# RPI-CM4-Breakout.net
KiCad netlist of a schematic drawn in EAGLE
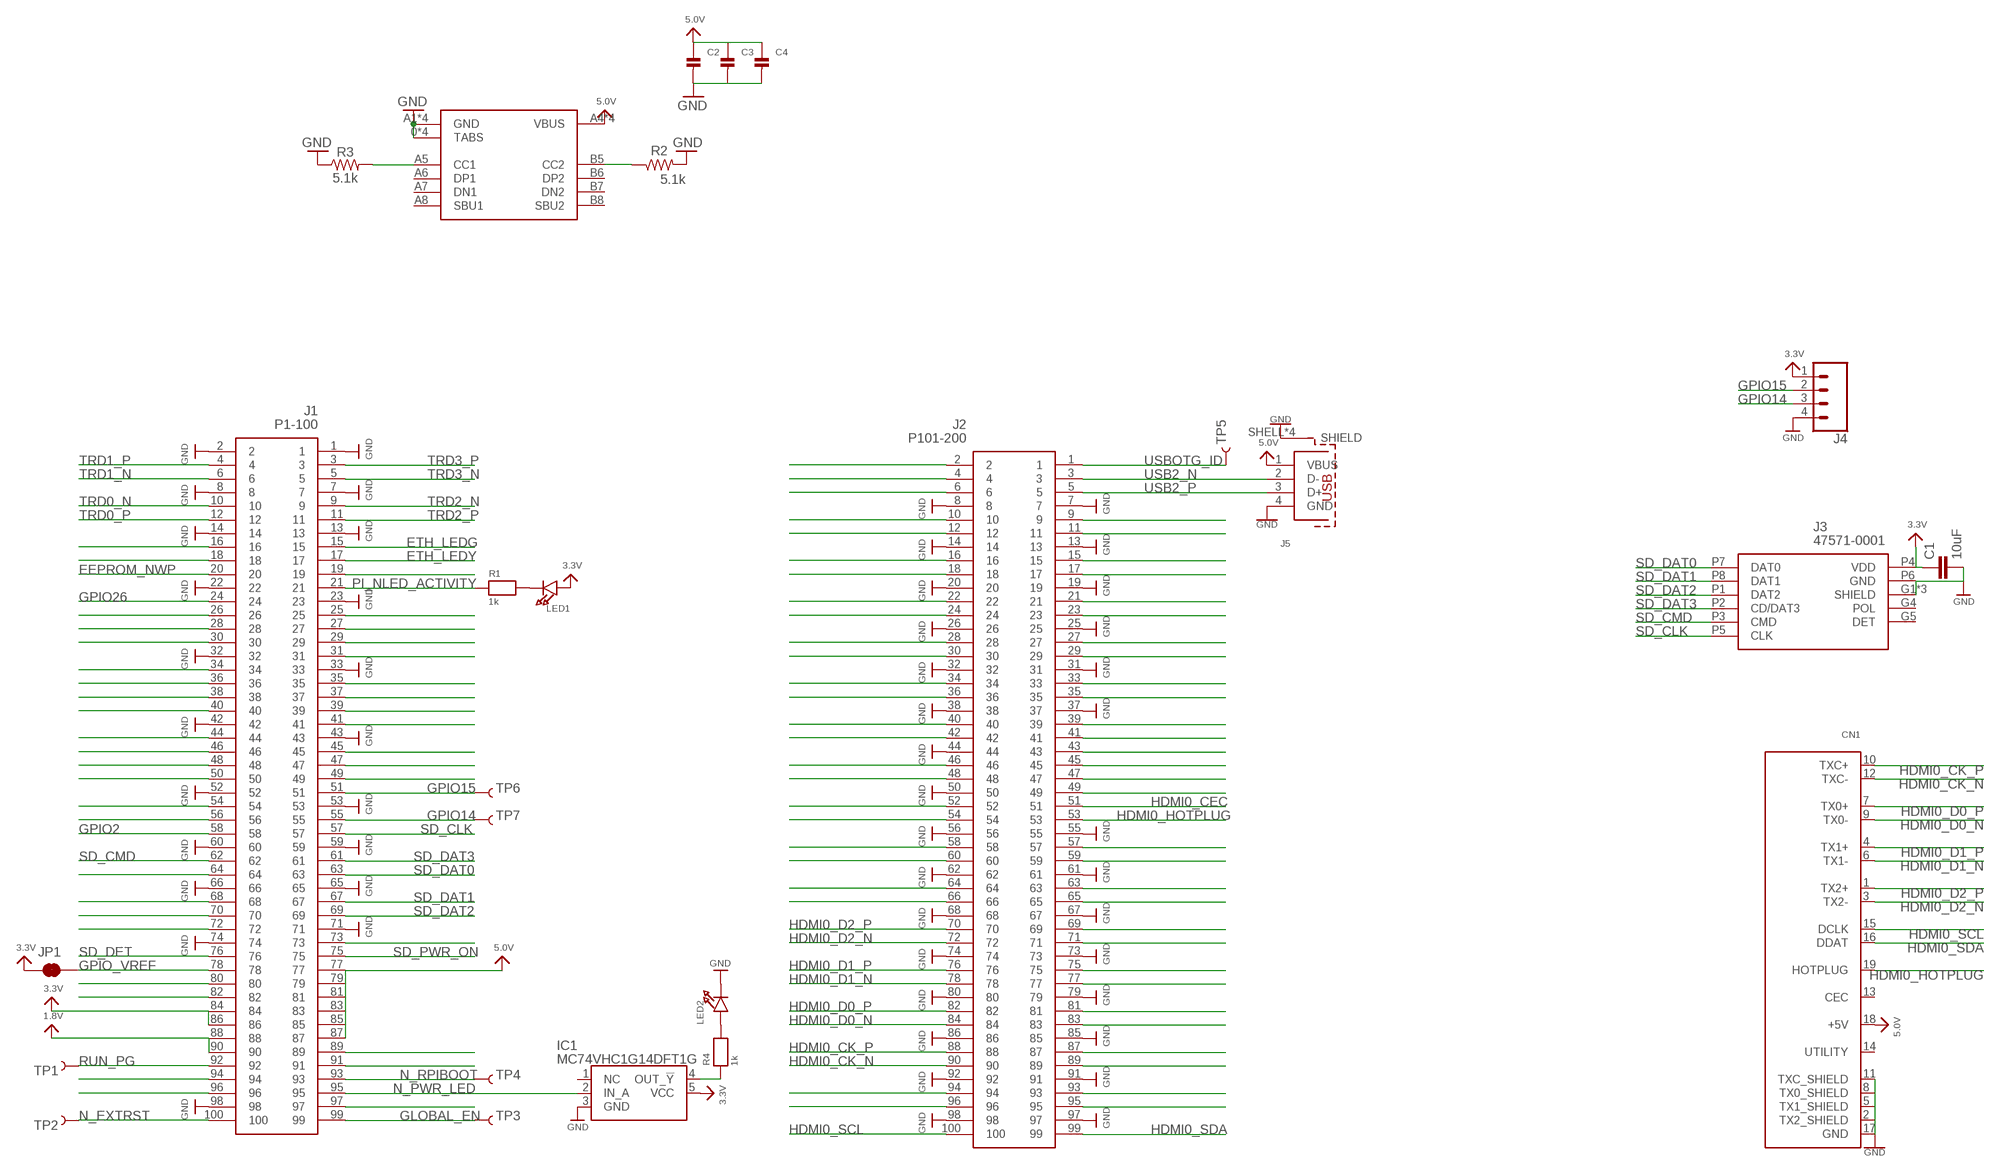
[diagram p0: schematic, sheet 1]

(export (version "E")
  (design (tool "Eeschema 10.0.6"))
  (components
    (comp (ref "C1")
      (value "10uF")
      (footprint "eagle-import:0603")
      (libsource (lib "eagle-import") (part "10UF-0603-6.3V-20%"))
    )
    (comp (ref "C2")
      (value "CAP_CERAMIC0402")
      (footprint "eagle-import:0402")
      (libsource (lib "eagle-import") (part "CAP_CERAMIC0402"))
    )
    (comp (ref "C3")
      (value "CAP_CERAMIC0402")
      (footprint "eagle-import:0402")
      (libsource (lib "eagle-import") (part "CAP_CERAMIC0402"))
    )
    (comp (ref "C4")
      (value "CAP_CERAMIC0402")
      (footprint "eagle-import:0402")
      (libsource (lib "eagle-import") (part "CAP_CERAMIC0402"))
    )
    (comp (ref "CN1")
      (value "HDMI_MOLEX_47151-0001")
      (footprint "eagle-import:HDMI_MOLEX_47151-0001")
      (libsource (lib "eagle-import") (part "HDMI_MOLEX_47151-0001"))
    )
    (comp (ref "IC1")
      (value "MC74VHC1G14DFT1G")
      (footprint "eagle-import:SOT65P210X110-5N")
      (fields (field (name "MOUSER_PART_NUMBER") "863-MC74VHC1G14DFT1G"))
      (libsource (lib "eagle-import") (part "MC74VHC1G14DFT1G"))
    )
    (comp (ref "J1")
      (value "P1-100")
      (footprint "eagle-import:DF40C100DS04V51")
      (fields
        (field (name "MANUFACTURER_PART_NUMBER") "DF40C-100DS-0.4V(51)")
        (field (name "MOUSER_PART_NUMBER") "798-DF40C100DS0.4V51")
      )
      (libsource (lib "eagle-import") (part "DF40C-100DS-0.4V_51_"))
    )
    (comp (ref "J2")
      (value "P101-200")
      (footprint "eagle-import:DF40C100DS04V51")
      (fields
        (field (name "MANUFACTURER_PART_NUMBER") "DF40C-100DS-0.4V(51)")
        (field (name "MOUSER_PART_NUMBER") "798-DF40C100DS0.4V51")
      )
      (libsource (lib "eagle-import") (part "DF40C-100DS-0.4V_51_"))
    )
    (comp (ref "J3")
      (value "47571-0001")
      (footprint "eagle-import:47571-0001")
      (fields (field (name "MOUSER_PART_NUMBER") "538-47571-0001"))
      (libsource (lib "eagle-import") (part "47571-0001"))
    )
    (comp (ref "J4")
      (value "CONN_04SMD_RA_FEMALE")
      (footprint "eagle-import:1X04_SMD_RA_FEMALE")
      (libsource (lib "eagle-import") (part "CONN_04SMD_RA_FEMALE"))
    )
    (comp (ref "J5")
      (value "629104190121")
      (footprint "eagle-import:629104190121")
      (libsource (lib "eagle-import") (part "629104190121"))
    )
    (comp (ref "JP1")
      (value "JUMPER-SMT_2_NC_TRACE_NO-SILK")
      (footprint "eagle-import:SMT-JUMPER_2_NC_TRACE_NO-SILK")
      (libsource (lib "eagle-import") (part "JUMPER-SMT_2_NC_TRACE_NO-SILK"))
    )
    (comp (ref "LED1")
      (value "LED0603")
      (footprint "eagle-import:CHIPLED_0603")
      (libsource (lib "eagle-import") (part "LED0603"))
    )
    (comp (ref "LED2")
      (value "LED0603")
      (footprint "eagle-import:CHIPLED_0603")
      (libsource (lib "eagle-import") (part "LED0603"))
    )
    (comp (ref "R1")
      (value "1k")
      (footprint "eagle-import:_0402MP")
      (libsource (lib "eagle-import") (part "RESISTOR_0402MP"))
    )
    (comp (ref "R2")
      (value "5.1k")
      (footprint "eagle-import:0603")
      (libsource (lib "eagle-import") (part "RESISTOR0603"))
    )
    (comp (ref "R3")
      (value "5.1k")
      (footprint "eagle-import:0603")
      (libsource (lib "eagle-import") (part "RESISTOR0603"))
    )
    (comp (ref "R4")
      (value "1k")
      (footprint "eagle-import:_0402MP")
      (libsource (lib "eagle-import") (part "RESISTOR_0402MP"))
    )
    (comp (ref "TP1")
      (value "TEST-POINT3X5")
      (footprint "eagle-import:PAD.03X.05")
      (libsource (lib "eagle-import") (part "TEST-POINT3X5"))
    )
    (comp (ref "TP2")
      (value "TEST-POINT3X5")
      (footprint "eagle-import:PAD.03X.05")
      (libsource (lib "eagle-import") (part "TEST-POINT3X5"))
    )
    (comp (ref "TP3")
      (value "TEST-POINT3X5")
      (footprint "eagle-import:PAD.03X.05")
      (libsource (lib "eagle-import") (part "TEST-POINT3X5"))
    )
    (comp (ref "TP4")
      (value "TEST-POINT3X5")
      (footprint "eagle-import:PAD.03X.05")
      (libsource (lib "eagle-import") (part "TEST-POINT3X5"))
    )
    (comp (ref "TP5")
      (value "TEST-POINT3X5")
      (footprint "eagle-import:PAD.03X.05")
      (libsource (lib "eagle-import") (part "TEST-POINT3X5"))
    )
    (comp (ref "TP6")
      (value "TEST-POINT3X5")
      (footprint "eagle-import:PAD.03X.05")
      (libsource (lib "eagle-import") (part "TEST-POINT3X5"))
    )
    (comp (ref "TP7")
      (value "TEST-POINT3X5")
      (footprint "eagle-import:PAD.03X.05")
      (libsource (lib "eagle-import") (part "TEST-POINT3X5"))
    )
    (comp (ref "U$59")
      (value "TYPE-C-31-M-12")
      (footprint "eagle-import:USB-TYPE-C_16PIN-MALE-TYPE-C-31-M-12")
      (libsource (lib "eagle-import") (part "TYPE-C-31-M-12"))
    )
  )
  (nets
    (net (code "1") (name "/EEPROM_NWP") (class "Default")
      (node (ref "J1") (pin "20") (pinfunction "20_20") (pintype "bidirectional"))
    )
    (net (code "2") (name "/ETH_LEDG") (class "Default")
      (node (ref "J1") (pin "15") (pinfunction "15_15") (pintype "bidirectional"))
    )
    (net (code "3") (name "/ETH_LEDY") (class "Default")
      (node (ref "J1") (pin "17") (pinfunction "17_17") (pintype "bidirectional"))
    )
    (net (code "4") (name "/GLOBAL_EN") (class "Default")
      (node (ref "J1") (pin "99") (pinfunction "99_99") (pintype "bidirectional"))
      (node (ref "TP3") (pin "P$1") (pinfunction "1_P$1") (pintype "bidirectional"))
    )
    (net (code "5") (name "/GPIO2") (class "Default")
      (node (ref "J1") (pin "58") (pinfunction "58_58") (pintype "bidirectional"))
    )
    (net (code "6") (name "/GPIO14") (class "Default")
      (node (ref "J1") (pin "55") (pinfunction "55_55") (pintype "bidirectional"))
      (node (ref "J4") (pin "3") (pinfunction "3_3") (pintype "passive"))
      (node (ref "TP7") (pin "P$1") (pinfunction "1_P$1") (pintype "bidirectional"))
    )
    (net (code "7") (name "/GPIO15") (class "Default")
      (node (ref "J1") (pin "51") (pinfunction "51_51") (pintype "bidirectional"))
      (node (ref "J4") (pin "2") (pinfunction "2_2") (pintype "passive"))
      (node (ref "TP6") (pin "P$1") (pinfunction "1_P$1") (pintype "bidirectional"))
    )
    (net (code "8") (name "/GPIO26") (class "Default")
      (node (ref "J1") (pin "24") (pinfunction "24_24") (pintype "bidirectional"))
    )
    (net (code "9") (name "/GPIO_VREF") (class "Default")
      (node (ref "J1") (pin "78") (pinfunction "78_78") (pintype "bidirectional"))
      (node (ref "JP1") (pin "2") (pinfunction "2_2") (pintype "passive"))
    )
    (net (code "10") (name "/HDMI0_CEC") (class "Default")
      (node (ref "J2") (pin "51") (pinfunction "51_51") (pintype "bidirectional"))
    )
    (net (code "11") (name "/HDMI0_CK_N") (class "Default")
      (node (ref "CN1") (pin "12") (pinfunction "TXC-_12") (pintype "bidirectional"))
      (node (ref "J2") (pin "90") (pinfunction "90_90") (pintype "bidirectional"))
    )
    (net (code "12") (name "/HDMI0_CK_P") (class "Default")
      (node (ref "CN1") (pin "10") (pinfunction "TXC+_10") (pintype "bidirectional"))
      (node (ref "J2") (pin "88") (pinfunction "88_88") (pintype "bidirectional"))
    )
    (net (code "13") (name "/HDMI0_D0_N") (class "Default")
      (node (ref "CN1") (pin "9") (pinfunction "TX0-_9") (pintype "bidirectional"))
      (node (ref "J2") (pin "84") (pinfunction "84_84") (pintype "bidirectional"))
    )
    (net (code "14") (name "/HDMI0_D0_P") (class "Default")
      (node (ref "CN1") (pin "7") (pinfunction "TX0+_7") (pintype "bidirectional"))
      (node (ref "J2") (pin "82") (pinfunction "82_82") (pintype "bidirectional"))
    )
    (net (code "15") (name "/HDMI0_D1_N") (class "Default")
      (node (ref "CN1") (pin "6") (pinfunction "TX1-_6") (pintype "bidirectional"))
      (node (ref "J2") (pin "78") (pinfunction "78_78") (pintype "bidirectional"))
    )
    (net (code "16") (name "/HDMI0_D1_P") (class "Default")
      (node (ref "CN1") (pin "4") (pinfunction "TX1+_4") (pintype "bidirectional"))
      (node (ref "J2") (pin "76") (pinfunction "76_76") (pintype "bidirectional"))
    )
    (net (code "17") (name "/HDMI0_D2_N") (class "Default")
      (node (ref "CN1") (pin "3") (pinfunction "TX2-_3") (pintype "bidirectional"))
      (node (ref "J2") (pin "72") (pinfunction "72_72") (pintype "bidirectional"))
    )
    (net (code "18") (name "/HDMI0_D2_P") (class "Default")
      (node (ref "CN1") (pin "1") (pinfunction "TX2+_1") (pintype "bidirectional"))
      (node (ref "J2") (pin "70") (pinfunction "70_70") (pintype "bidirectional"))
    )
    (net (code "19") (name "/HDMI0_HOTPLUG") (class "Default")
      (node (ref "CN1") (pin "19") (pinfunction "HOTPLUG_19") (pintype "bidirectional"))
      (node (ref "J2") (pin "53") (pinfunction "53_53") (pintype "bidirectional"))
    )
    (net (code "20") (name "/HDMI0_SCL") (class "Default")
      (node (ref "CN1") (pin "15") (pinfunction "DCLK_15") (pintype "bidirectional"))
      (node (ref "J2") (pin "100") (pinfunction "100_100") (pintype "bidirectional"))
    )
    (net (code "21") (name "/HDMI0_SDA") (class "Default")
      (node (ref "CN1") (pin "16") (pinfunction "DDAT_16") (pintype "bidirectional"))
      (node (ref "J2") (pin "99") (pinfunction "99_99") (pintype "bidirectional"))
    )
    (net (code "22") (name "/N_EXTRST") (class "Default")
      (node (ref "J1") (pin "100") (pinfunction "100_100") (pintype "bidirectional"))
      (node (ref "TP2") (pin "P$1") (pinfunction "1_P$1") (pintype "bidirectional"))
    )
    (net (code "23") (name "/N_PWR_LED") (class "Default")
      (node (ref "IC1") (pin "2") (pinfunction "IN_A_2") (pintype "input"))
      (node (ref "J1") (pin "95") (pinfunction "95_95") (pintype "bidirectional"))
    )
    (net (code "24") (name "/N_RPIBOOT") (class "Default")
      (node (ref "J1") (pin "93") (pinfunction "93_93") (pintype "bidirectional"))
      (node (ref "TP4") (pin "P$1") (pinfunction "1_P$1") (pintype "bidirectional"))
    )
    (net (code "25") (name "/PI_NLED_ACTIVITY") (class "Default")
      (node (ref "J1") (pin "21") (pinfunction "21_21") (pintype "bidirectional"))
      (node (ref "R1") (pin "1") (pinfunction "1_1") (pintype "passive"))
    )
    (net (code "26") (name "/RUN_PG") (class "Default")
      (node (ref "J1") (pin "92") (pinfunction "92_92") (pintype "bidirectional"))
      (node (ref "TP1") (pin "P$1") (pinfunction "1_P$1") (pintype "bidirectional"))
    )
    (net (code "27") (name "/SD_CLK") (class "Default")
      (node (ref "J1") (pin "57") (pinfunction "57_57") (pintype "bidirectional"))
      (node (ref "J3") (pin "P5") (pinfunction "CLK_P5") (pintype "bidirectional"))
    )
    (net (code "28") (name "/SD_CMD") (class "Default")
      (node (ref "J1") (pin "62") (pinfunction "62_62") (pintype "bidirectional"))
      (node (ref "J3") (pin "P3") (pinfunction "CMD_P3") (pintype "bidirectional"))
    )
    (net (code "29") (name "/SD_DAT0") (class "Default")
      (node (ref "J1") (pin "63") (pinfunction "63_63") (pintype "bidirectional"))
      (node (ref "J3") (pin "P7") (pinfunction "DAT0_P7") (pintype "bidirectional"))
    )
    (net (code "30") (name "/SD_DAT1") (class "Default")
      (node (ref "J1") (pin "67") (pinfunction "67_67") (pintype "bidirectional"))
      (node (ref "J3") (pin "P8") (pinfunction "DAT1_P8") (pintype "bidirectional"))
    )
    (net (code "31") (name "/SD_DAT2") (class "Default")
      (node (ref "J1") (pin "69") (pinfunction "69_69") (pintype "bidirectional"))
      (node (ref "J3") (pin "P1") (pinfunction "DAT2_P1") (pintype "bidirectional"))
    )
    (net (code "32") (name "/SD_DAT3") (class "Default")
      (node (ref "J1") (pin "61") (pinfunction "61_61") (pintype "bidirectional"))
      (node (ref "J3") (pin "P2") (pinfunction "CD/DAT3_P2") (pintype "bidirectional"))
    )
    (net (code "33") (name "/SD_DET") (class "Default")
      (node (ref "J1") (pin "76") (pinfunction "76_76") (pintype "bidirectional"))
    )
    (net (code "34") (name "/SD_PWR_ON") (class "Default")
      (node (ref "J1") (pin "75") (pinfunction "75_75") (pintype "bidirectional"))
    )
    (net (code "35") (name "/TRD0_N") (class "Default")
      (node (ref "J1") (pin "10") (pinfunction "10_10") (pintype "bidirectional"))
    )
    (net (code "36") (name "/TRD0_P") (class "Default")
      (node (ref "J1") (pin "12") (pinfunction "12_12") (pintype "bidirectional"))
    )
    (net (code "37") (name "/TRD1_N") (class "Default")
      (node (ref "J1") (pin "6") (pinfunction "6_6") (pintype "bidirectional"))
    )
    (net (code "38") (name "/TRD1_P") (class "Default")
      (node (ref "J1") (pin "4") (pinfunction "4_4") (pintype "bidirectional"))
    )
    (net (code "39") (name "/TRD2_N") (class "Default")
      (node (ref "J1") (pin "9") (pinfunction "9_9") (pintype "bidirectional"))
    )
    (net (code "40") (name "/TRD2_P") (class "Default")
      (node (ref "J1") (pin "11") (pinfunction "11_11") (pintype "bidirectional"))
    )
    (net (code "41") (name "/TRD3_N") (class "Default")
      (node (ref "J1") (pin "5") (pinfunction "5_5") (pintype "bidirectional"))
    )
    (net (code "42") (name "/TRD3_P") (class "Default")
      (node (ref "J1") (pin "3") (pinfunction "3_3") (pintype "bidirectional"))
    )
    (net (code "43") (name "/USB2_N") (class "Default")
      (node (ref "J2") (pin "3") (pinfunction "3_3") (pintype "bidirectional"))
      (node (ref "J5") (pin "2") (pinfunction "D-_2") (pintype "bidirectional"))
    )
    (net (code "44") (name "/USB2_P") (class "Default")
      (node (ref "J2") (pin "5") (pinfunction "5_5") (pintype "bidirectional"))
      (node (ref "J5") (pin "3") (pinfunction "D+_3") (pintype "bidirectional"))
    )
    (net (code "45") (name "/USBOTG_ID") (class "Default")
      (node (ref "J2") (pin "1") (pinfunction "1_1") (pintype "bidirectional"))
      (node (ref "TP5") (pin "P$1") (pinfunction "1_P$1") (pintype "bidirectional"))
    )
    (net (code "46") (name "1.8V") (class "Default")
      (node (ref "J1") (pin "88") (pinfunction "88_88") (pintype "bidirectional"))
      (node (ref "J1") (pin "90") (pinfunction "90_90") (pintype "bidirectional"))
    )
    (net (code "47") (name "3.3V") (class "Default")
      (node (ref "C1") (pin "1") (pinfunction "1_1") (pintype "passive"))
      (node (ref "IC1") (pin "5") (pinfunction "VCC_5") (pintype "power_in"))
      (node (ref "J1") (pin "84") (pinfunction "84_84") (pintype "bidirectional"))
      (node (ref "J1") (pin "86") (pinfunction "86_86") (pintype "bidirectional"))
      (node (ref "J3") (pin "P4") (pinfunction "VDD_P4") (pintype "bidirectional"))
      (node (ref "J4") (pin "1") (pinfunction "1_1") (pintype "passive"))
      (node (ref "JP1") (pin "1") (pinfunction "1_1") (pintype "passive"))
      (node (ref "LED1") (pin "A") (pinfunction "A_A") (pintype "passive"))
    )
    (net (code "48") (name "5.0V") (class "Default")
      (node (ref "C2") (pin "1") (pinfunction "P$1_1") (pintype "passive"))
      (node (ref "C3") (pin "1") (pinfunction "P$1_1") (pintype "passive"))
      (node (ref "C4") (pin "1") (pinfunction "P$1_1") (pintype "passive"))
      (node (ref "CN1") (pin "18") (pinfunction "+5V_18") (pintype "power_in"))
      (node (ref "J1") (pin "77") (pinfunction "77_77") (pintype "bidirectional"))
      (node (ref "J1") (pin "79") (pinfunction "79_79") (pintype "bidirectional"))
      (node (ref "J1") (pin "81") (pinfunction "81_81") (pintype "bidirectional"))
      (node (ref "J1") (pin "83") (pinfunction "83_83") (pintype "bidirectional"))
      (node (ref "J1") (pin "85") (pinfunction "85_85") (pintype "bidirectional"))
      (node (ref "J1") (pin "87") (pinfunction "87_87") (pintype "bidirectional"))
      (node (ref "J5") (pin "1") (pinfunction "VBUS_1") (pintype "bidirectional"))
      (node (ref "U$59") (pin "A4") (pinfunction "VBUS_A4") (pintype "bidirectional"))
      (node (ref "U$59") (pin "A9") (pinfunction "VBUS_A9") (pintype "bidirectional"))
      (node (ref "U$59") (pin "B4") (pinfunction "VBUS_B4") (pintype "bidirectional"))
      (node (ref "U$59") (pin "B9") (pinfunction "VBUS_B9") (pintype "bidirectional"))
    )
    (net (code "49") (name "GND") (class "Default")
      (node (ref "C1") (pin "2") (pinfunction "2_2") (pintype "passive"))
      (node (ref "C2") (pin "2") (pinfunction "P$2_2") (pintype "passive"))
      (node (ref "C3") (pin "2") (pinfunction "P$2_2") (pintype "passive"))
      (node (ref "C4") (pin "2") (pinfunction "P$2_2") (pintype "passive"))
      (node (ref "CN1") (pin "11") (pinfunction "TXC_SHIELD_11") (pintype "power_in"))
      (node (ref "CN1") (pin "17") (pinfunction "GND_17") (pintype "power_in"))
      (node (ref "CN1") (pin "2") (pinfunction "TX2_SHIELD_2") (pintype "power_in"))
      (node (ref "CN1") (pin "5") (pinfunction "TX1_SHIELD_5") (pintype "power_in"))
      (node (ref "CN1") (pin "8") (pinfunction "TX0_SHIELD_8") (pintype "power_in"))
      (node (ref "IC1") (pin "3") (pinfunction "GND_3") (pintype "power_in"))
      (node (ref "J1") (pin "1") (pinfunction "1_1") (pintype "bidirectional"))
      (node (ref "J1") (pin "13") (pinfunction "13_13") (pintype "bidirectional"))
      (node (ref "J1") (pin "14") (pinfunction "14_14") (pintype "bidirectional"))
      (node (ref "J1") (pin "2") (pinfunction "2_2") (pintype "bidirectional"))
      (node (ref "J1") (pin "22") (pinfunction "22_22") (pintype "bidirectional"))
      (node (ref "J1") (pin "23") (pinfunction "23_23") (pintype "bidirectional"))
      (node (ref "J1") (pin "32") (pinfunction "32_32") (pintype "bidirectional"))
      (node (ref "J1") (pin "33") (pinfunction "33_33") (pintype "bidirectional"))
      (node (ref "J1") (pin "42") (pinfunction "42_42") (pintype "bidirectional"))
      (node (ref "J1") (pin "43") (pinfunction "43_43") (pintype "bidirectional"))
      (node (ref "J1") (pin "52") (pinfunction "52_52") (pintype "bidirectional"))
      (node (ref "J1") (pin "53") (pinfunction "53_53") (pintype "bidirectional"))
      (node (ref "J1") (pin "59") (pinfunction "59_59") (pintype "bidirectional"))
      (node (ref "J1") (pin "60") (pinfunction "60_60") (pintype "bidirectional"))
      (node (ref "J1") (pin "65") (pinfunction "65_65") (pintype "bidirectional"))
      (node (ref "J1") (pin "66") (pinfunction "66_66") (pintype "bidirectional"))
      (node (ref "J1") (pin "7") (pinfunction "7_7") (pintype "bidirectional"))
      (node (ref "J1") (pin "71") (pinfunction "71_71") (pintype "bidirectional"))
      (node (ref "J1") (pin "74") (pinfunction "74_74") (pintype "bidirectional"))
      (node (ref "J1") (pin "8") (pinfunction "8_8") (pintype "bidirectional"))
      (node (ref "J1") (pin "98") (pinfunction "98_98") (pintype "bidirectional"))
      (node (ref "J2") (pin "13") (pinfunction "13_13") (pintype "bidirectional"))
      (node (ref "J2") (pin "14") (pinfunction "14_14") (pintype "bidirectional"))
      (node (ref "J2") (pin "19") (pinfunction "19_19") (pintype "bidirectional"))
      (node (ref "J2") (pin "20") (pinfunction "20_20") (pintype "bidirectional"))
      (node (ref "J2") (pin "25") (pinfunction "25_25") (pintype "bidirectional"))
      (node (ref "J2") (pin "26") (pinfunction "26_26") (pintype "bidirectional"))
      (node (ref "J2") (pin "31") (pinfunction "31_31") (pintype "bidirectional"))
      (node (ref "J2") (pin "32") (pinfunction "32_32") (pintype "bidirectional"))
      (node (ref "J2") (pin "37") (pinfunction "37_37") (pintype "bidirectional"))
      (node (ref "J2") (pin "38") (pinfunction "38_38") (pintype "bidirectional"))
      (node (ref "J2") (pin "44") (pinfunction "44_44") (pintype "bidirectional"))
      (node (ref "J2") (pin "50") (pinfunction "50_50") (pintype "bidirectional"))
      (node (ref "J2") (pin "55") (pinfunction "55_55") (pintype "bidirectional"))
      (node (ref "J2") (pin "56") (pinfunction "56_56") (pintype "bidirectional"))
      (node (ref "J2") (pin "61") (pinfunction "61_61") (pintype "bidirectional"))
      (node (ref "J2") (pin "62") (pinfunction "62_62") (pintype "bidirectional"))
      (node (ref "J2") (pin "67") (pinfunction "67_67") (pintype "bidirectional"))
      (node (ref "J2") (pin "68") (pinfunction "68_68") (pintype "bidirectional"))
      (node (ref "J2") (pin "7") (pinfunction "7_7") (pintype "bidirectional"))
      (node (ref "J2") (pin "73") (pinfunction "73_73") (pintype "bidirectional"))
      (node (ref "J2") (pin "74") (pinfunction "74_74") (pintype "bidirectional"))
      (node (ref "J2") (pin "79") (pinfunction "79_79") (pintype "bidirectional"))
      (node (ref "J2") (pin "8") (pinfunction "8_8") (pintype "bidirectional"))
      (node (ref "J2") (pin "80") (pinfunction "80_80") (pintype "bidirectional"))
      (node (ref "J2") (pin "85") (pinfunction "85_85") (pintype "bidirectional"))
      (node (ref "J2") (pin "86") (pinfunction "86_86") (pintype "bidirectional"))
      (node (ref "J2") (pin "91") (pinfunction "91_91") (pintype "bidirectional"))
      (node (ref "J2") (pin "92") (pinfunction "92_92") (pintype "bidirectional"))
      (node (ref "J2") (pin "97") (pinfunction "97_97") (pintype "bidirectional"))
      (node (ref "J2") (pin "98") (pinfunction "98_98") (pintype "bidirectional"))
      (node (ref "J3") (pin "G1") (pinfunction "SHIELD_G1") (pintype "bidirectional"))
      (node (ref "J3") (pin "G2") (pinfunction "SHIELD_G2") (pintype "bidirectional"))
      (node (ref "J3") (pin "G3") (pinfunction "SHIELD_G3") (pintype "bidirectional"))
      (node (ref "J3") (pin "P6") (pinfunction "GND_P6") (pintype "bidirectional"))
      (node (ref "J4") (pin "4") (pinfunction "4_4") (pintype "passive"))
      (node (ref "J5") (pin "4") (pinfunction "GND_4") (pintype "bidirectional"))
      (node (ref "J5") (pin "SHELL") (pinfunction "SHIELD_SHELL") (pintype "bidirectional"))
      (node (ref "J5") (pin "SHELL1") (pinfunction "SHIELD_SHELL1") (pintype "bidirectional"))
      (node (ref "J5") (pin "SHELL2") (pinfunction "SHIELD_SHELL2") (pintype "bidirectional"))
      (node (ref "J5") (pin "SHELL3") (pinfunction "SHIELD_SHELL3") (pintype "bidirectional"))
      (node (ref "LED2") (pin "C") (pinfunction "C_C") (pintype "passive"))
      (node (ref "R2") (pin "2") (pinfunction "2_2") (pintype "passive"))
      (node (ref "R3") (pin "1") (pinfunction "1_1") (pintype "passive"))
      (node (ref "U$59") (pin "0") (pinfunction "TABS_0") (pintype "bidirectional"))
      (node (ref "U$59") (pin "0-1") (pinfunction "TABS_0-1") (pintype "bidirectional"))
      (node (ref "U$59") (pin "0-2") (pinfunction "TABS_0-2") (pintype "bidirectional"))
      (node (ref "U$59") (pin "0-3") (pinfunction "TABS_0-3") (pintype "bidirectional"))
      (node (ref "U$59") (pin "A1") (pinfunction "GND_A1") (pintype "bidirectional"))
      (node (ref "U$59") (pin "A12") (pinfunction "GND_A12") (pintype "bidirectional"))
      (node (ref "U$59") (pin "B1") (pinfunction "GND_B1") (pintype "bidirectional"))
      (node (ref "U$59") (pin "B12") (pinfunction "GND_B12") (pintype "bidirectional"))
    )
    (net (code "50") (name "Net-(IC1-OUT_~{Y})") (class "Default")
      (node (ref "IC1") (pin "4") (pinfunction "OUT_~{Y}_4") (pintype "output"))
      (node (ref "R4") (pin "1") (pinfunction "1_1") (pintype "passive"))
    )
    (net (code "51") (name "Net-(LED1-PadC)") (class "Default")
      (node (ref "LED1") (pin "C") (pinfunction "C_C") (pintype "passive"))
      (node (ref "R1") (pin "2") (pinfunction "2_2") (pintype "passive"))
    )
    (net (code "52") (name "Net-(LED2-PadA)") (class "Default")
      (node (ref "LED2") (pin "A") (pinfunction "A_A") (pintype "passive"))
      (node (ref "R4") (pin "2") (pinfunction "2_2") (pintype "passive"))
    )
    (net (code "53") (name "Net-(U$59-CC1)") (class "Default")
      (node (ref "R3") (pin "2") (pinfunction "2_2") (pintype "passive"))
      (node (ref "U$59") (pin "A5") (pinfunction "CC1_A5") (pintype "bidirectional"))
    )
    (net (code "54") (name "Net-(U$59-CC2)") (class "Default")
      (node (ref "R2") (pin "1") (pinfunction "1_1") (pintype "passive"))
      (node (ref "U$59") (pin "B5") (pinfunction "CC2_B5") (pintype "bidirectional"))
    )
    (net (code "55") (name "unconnected-(CN1A-CEC-Pad13)") (class "Default")
      (node (ref "CN1") (pin "13") (pinfunction "CEC_13") (pintype "bidirectional"))
    )
    (net (code "56") (name "unconnected-(CN1A-UTILITY-Pad14)") (class "Default")
      (node (ref "CN1") (pin "14") (pinfunction "UTILITY_14") (pintype "bidirectional"))
    )
    (net (code "57") (name "unconnected-(IC1-NC-Pad1)") (class "Default")
      (node (ref "IC1") (pin "1") (pinfunction "NC_1") (pintype "no_connect"))
    )
    (net (code "58") (name "unconnected-(J1-Pad16)") (class "Default")
      (node (ref "J1") (pin "16") (pinfunction "16_16") (pintype "bidirectional"))
    )
    (net (code "59") (name "unconnected-(J1-Pad18)") (class "Default")
      (node (ref "J1") (pin "18") (pinfunction "18_18") (pintype "bidirectional"))
    )
    (net (code "60") (name "unconnected-(J1-Pad19)") (class "Default")
      (node (ref "J1") (pin "19") (pinfunction "19_19") (pintype "bidirectional"))
    )
    (net (code "61") (name "unconnected-(J1-Pad25)") (class "Default")
      (node (ref "J1") (pin "25") (pinfunction "25_25") (pintype "bidirectional"))
    )
    (net (code "62") (name "unconnected-(J1-Pad26)") (class "Default")
      (node (ref "J1") (pin "26") (pinfunction "26_26") (pintype "bidirectional"))
    )
    (net (code "63") (name "unconnected-(J1-Pad27)") (class "Default")
      (node (ref "J1") (pin "27") (pinfunction "27_27") (pintype "bidirectional"))
    )
    (net (code "64") (name "unconnected-(J1-Pad28)") (class "Default")
      (node (ref "J1") (pin "28") (pinfunction "28_28") (pintype "bidirectional"))
    )
    (net (code "65") (name "unconnected-(J1-Pad29)") (class "Default")
      (node (ref "J1") (pin "29") (pinfunction "29_29") (pintype "bidirectional"))
    )
    (net (code "66") (name "unconnected-(J1-Pad30)") (class "Default")
      (node (ref "J1") (pin "30") (pinfunction "30_30") (pintype "bidirectional"))
    )
    (net (code "67") (name "unconnected-(J1-Pad31)") (class "Default")
      (node (ref "J1") (pin "31") (pinfunction "31_31") (pintype "bidirectional"))
    )
    (net (code "68") (name "unconnected-(J1-Pad34)") (class "Default")
      (node (ref "J1") (pin "34") (pinfunction "34_34") (pintype "bidirectional"))
    )
    (net (code "69") (name "unconnected-(J1-Pad35)") (class "Default")
      (node (ref "J1") (pin "35") (pinfunction "35_35") (pintype "bidirectional"))
    )
    (net (code "70") (name "unconnected-(J1-Pad36)") (class "Default")
      (node (ref "J1") (pin "36") (pinfunction "36_36") (pintype "bidirectional"))
    )
    (net (code "71") (name "unconnected-(J1-Pad37)") (class "Default")
      (node (ref "J1") (pin "37") (pinfunction "37_37") (pintype "bidirectional"))
    )
    (net (code "72") (name "unconnected-(J1-Pad38)") (class "Default")
      (node (ref "J1") (pin "38") (pinfunction "38_38") (pintype "bidirectional"))
    )
    (net (code "73") (name "unconnected-(J1-Pad39)") (class "Default")
      (node (ref "J1") (pin "39") (pinfunction "39_39") (pintype "bidirectional"))
    )
    (net (code "74") (name "unconnected-(J1-Pad40)") (class "Default")
      (node (ref "J1") (pin "40") (pinfunction "40_40") (pintype "bidirectional"))
    )
    (net (code "75") (name "unconnected-(J1-Pad41)") (class "Default")
      (node (ref "J1") (pin "41") (pinfunction "41_41") (pintype "bidirectional"))
    )
    (net (code "76") (name "unconnected-(J1-Pad44)") (class "Default")
      (node (ref "J1") (pin "44") (pinfunction "44_44") (pintype "bidirectional"))
    )
    (net (code "77") (name "unconnected-(J1-Pad45)") (class "Default")
      (node (ref "J1") (pin "45") (pinfunction "45_45") (pintype "bidirectional"))
    )
    (net (code "78") (name "unconnected-(J1-Pad46)") (class "Default")
      (node (ref "J1") (pin "46") (pinfunction "46_46") (pintype "bidirectional"))
    )
    (net (code "79") (name "unconnected-(J1-Pad47)") (class "Default")
      (node (ref "J1") (pin "47") (pinfunction "47_47") (pintype "bidirectional"))
    )
    (net (code "80") (name "unconnected-(J1-Pad48)") (class "Default")
      (node (ref "J1") (pin "48") (pinfunction "48_48") (pintype "bidirectional"))
    )
    (net (code "81") (name "unconnected-(J1-Pad49)") (class "Default")
      (node (ref "J1") (pin "49") (pinfunction "49_49") (pintype "bidirectional"))
    )
    (net (code "82") (name "unconnected-(J1-Pad50)") (class "Default")
      (node (ref "J1") (pin "50") (pinfunction "50_50") (pintype "bidirectional"))
    )
    (net (code "83") (name "unconnected-(J1-Pad54)") (class "Default")
      (node (ref "J1") (pin "54") (pinfunction "54_54") (pintype "bidirectional"))
    )
    (net (code "84") (name "unconnected-(J1-Pad56)") (class "Default")
      (node (ref "J1") (pin "56") (pinfunction "56_56") (pintype "bidirectional"))
    )
    (net (code "85") (name "unconnected-(J1-Pad64)") (class "Default")
      (node (ref "J1") (pin "64") (pinfunction "64_64") (pintype "bidirectional"))
    )
    (net (code "86") (name "unconnected-(J1-Pad68)") (class "Default")
      (node (ref "J1") (pin "68") (pinfunction "68_68") (pintype "bidirectional"))
    )
    (net (code "87") (name "unconnected-(J1-Pad70)") (class "Default")
      (node (ref "J1") (pin "70") (pinfunction "70_70") (pintype "bidirectional"))
    )
    (net (code "88") (name "unconnected-(J1-Pad72)") (class "Default")
      (node (ref "J1") (pin "72") (pinfunction "72_72") (pintype "bidirectional"))
    )
    (net (code "89") (name "unconnected-(J1-Pad73)") (class "Default")
      (node (ref "J1") (pin "73") (pinfunction "73_73") (pintype "bidirectional"))
    )
    (net (code "90") (name "unconnected-(J1-Pad80)") (class "Default")
      (node (ref "J1") (pin "80") (pinfunction "80_80") (pintype "bidirectional"))
    )
    (net (code "91") (name "unconnected-(J1-Pad82)") (class "Default")
      (node (ref "J1") (pin "82") (pinfunction "82_82") (pintype "bidirectional"))
    )
    (net (code "92") (name "unconnected-(J1-Pad89)") (class "Default")
      (node (ref "J1") (pin "89") (pinfunction "89_89") (pintype "bidirectional"))
    )
    (net (code "93") (name "unconnected-(J1-Pad91)") (class "Default")
      (node (ref "J1") (pin "91") (pinfunction "91_91") (pintype "bidirectional"))
    )
    (net (code "94") (name "unconnected-(J1-Pad94)") (class "Default")
      (node (ref "J1") (pin "94") (pinfunction "94_94") (pintype "bidirectional"))
    )
    (net (code "95") (name "unconnected-(J1-Pad96)") (class "Default")
      (node (ref "J1") (pin "96") (pinfunction "96_96") (pintype "bidirectional"))
    )
    (net (code "96") (name "unconnected-(J1-Pad97)") (class "Default")
      (node (ref "J1") (pin "97") (pinfunction "97_97") (pintype "bidirectional"))
    )
    (net (code "97") (name "unconnected-(J2-Pad2)") (class "Default")
      (node (ref "J2") (pin "2") (pinfunction "2_2") (pintype "bidirectional"))
    )
    (net (code "98") (name "unconnected-(J2-Pad4)") (class "Default")
      (node (ref "J2") (pin "4") (pinfunction "4_4") (pintype "bidirectional"))
    )
    (net (code "99") (name "unconnected-(J2-Pad6)") (class "Default")
      (node (ref "J2") (pin "6") (pinfunction "6_6") (pintype "bidirectional"))
    )
    (net (code "100") (name "unconnected-(J2-Pad9)") (class "Default")
      (node (ref "J2") (pin "9") (pinfunction "9_9") (pintype "bidirectional"))
    )
    (net (code "101") (name "unconnected-(J2-Pad10)") (class "Default")
      (node (ref "J2") (pin "10") (pinfunction "10_10") (pintype "bidirectional"))
    )
    (net (code "102") (name "unconnected-(J2-Pad11)") (class "Default")
      (node (ref "J2") (pin "11") (pinfunction "11_11") (pintype "bidirectional"))
    )
    (net (code "103") (name "unconnected-(J2-Pad12)") (class "Default")
      (node (ref "J2") (pin "12") (pinfunction "12_12") (pintype "bidirectional"))
    )
    (net (code "104") (name "unconnected-(J2-Pad15)") (class "Default")
      (node (ref "J2") (pin "15") (pinfunction "15_15") (pintype "bidirectional"))
    )
    (net (code "105") (name "unconnected-(J2-Pad16)") (class "Default")
      (node (ref "J2") (pin "16") (pinfunction "16_16") (pintype "bidirectional"))
    )
    (net (code "106") (name "unconnected-(J2-Pad17)") (class "Default")
      (node (ref "J2") (pin "17") (pinfunction "17_17") (pintype "bidirectional"))
    )
    (net (code "107") (name "unconnected-(J2-Pad18)") (class "Default")
      (node (ref "J2") (pin "18") (pinfunction "18_18") (pintype "bidirectional"))
    )
    (net (code "108") (name "unconnected-(J2-Pad21)") (class "Default")
      (node (ref "J2") (pin "21") (pinfunction "21_21") (pintype "bidirectional"))
    )
    (net (code "109") (name "unconnected-(J2-Pad22)") (class "Default")
      (node (ref "J2") (pin "22") (pinfunction "22_22") (pintype "bidirectional"))
    )
    (net (code "110") (name "unconnected-(J2-Pad23)") (class "Default")
      (node (ref "J2") (pin "23") (pinfunction "23_23") (pintype "bidirectional"))
    )
    (net (code "111") (name "unconnected-(J2-Pad24)") (class "Default")
      (node (ref "J2") (pin "24") (pinfunction "24_24") (pintype "bidirectional"))
    )
    (net (code "112") (name "unconnected-(J2-Pad27)") (class "Default")
      (node (ref "J2") (pin "27") (pinfunction "27_27") (pintype "bidirectional"))
    )
    (net (code "113") (name "unconnected-(J2-Pad28)") (class "Default")
      (node (ref "J2") (pin "28") (pinfunction "28_28") (pintype "bidirectional"))
    )
    (net (code "114") (name "unconnected-(J2-Pad29)") (class "Default")
      (node (ref "J2") (pin "29") (pinfunction "29_29") (pintype "bidirectional"))
    )
    (net (code "115") (name "unconnected-(J2-Pad30)") (class "Default")
      (node (ref "J2") (pin "30") (pinfunction "30_30") (pintype "bidirectional"))
    )
    (net (code "116") (name "unconnected-(J2-Pad33)") (class "Default")
      (node (ref "J2") (pin "33") (pinfunction "33_33") (pintype "bidirectional"))
    )
    (net (code "117") (name "unconnected-(J2-Pad34)") (class "Default")
      (node (ref "J2") (pin "34") (pinfunction "34_34") (pintype "bidirectional"))
    )
    (net (code "118") (name "unconnected-(J2-Pad35)") (class "Default")
      (node (ref "J2") (pin "35") (pinfunction "35_35") (pintype "bidirectional"))
    )
    (net (code "119") (name "unconnected-(J2-Pad36)") (class "Default")
      (node (ref "J2") (pin "36") (pinfunction "36_36") (pintype "bidirectional"))
    )
    (net (code "120") (name "unconnected-(J2-Pad39)") (class "Default")
      (node (ref "J2") (pin "39") (pinfunction "39_39") (pintype "bidirectional"))
    )
    (net (code "121") (name "unconnected-(J2-Pad40)") (class "Default")
      (node (ref "J2") (pin "40") (pinfunction "40_40") (pintype "bidirectional"))
    )
    (net (code "122") (name "unconnected-(J2-Pad41)") (class "Default")
      (node (ref "J2") (pin "41") (pinfunction "41_41") (pintype "bidirectional"))
    )
    (net (code "123") (name "unconnected-(J2-Pad42)") (class "Default")
      (node (ref "J2") (pin "42") (pinfunction "42_42") (pintype "bidirectional"))
    )
    (net (code "124") (name "unconnected-(J2-Pad43)") (class "Default")
      (node (ref "J2") (pin "43") (pinfunction "43_43") (pintype "bidirectional"))
    )
    (net (code "125") (name "unconnected-(J2-Pad45)") (class "Default")
      (node (ref "J2") (pin "45") (pinfunction "45_45") (pintype "bidirectional"))
    )
    (net (code "126") (name "unconnected-(J2-Pad46)") (class "Default")
      (node (ref "J2") (pin "46") (pinfunction "46_46") (pintype "bidirectional"))
    )
    (net (code "127") (name "unconnected-(J2-Pad47)") (class "Default")
      (node (ref "J2") (pin "47") (pinfunction "47_47") (pintype "bidirectional"))
    )
    (net (code "128") (name "unconnected-(J2-Pad48)") (class "Default")
      (node (ref "J2") (pin "48") (pinfunction "48_48") (pintype "bidirectional"))
    )
    (net (code "129") (name "unconnected-(J2-Pad49)") (class "Default")
      (node (ref "J2") (pin "49") (pinfunction "49_49") (pintype "bidirectional"))
    )
    (net (code "130") (name "unconnected-(J2-Pad52)") (class "Default")
      (node (ref "J2") (pin "52") (pinfunction "52_52") (pintype "bidirectional"))
    )
    (net (code "131") (name "unconnected-(J2-Pad54)") (class "Default")
      (node (ref "J2") (pin "54") (pinfunction "54_54") (pintype "bidirectional"))
    )
    (net (code "132") (name "unconnected-(J2-Pad57)") (class "Default")
      (node (ref "J2") (pin "57") (pinfunction "57_57") (pintype "bidirectional"))
    )
    (net (code "133") (name "unconnected-(J2-Pad58)") (class "Default")
      (node (ref "J2") (pin "58") (pinfunction "58_58") (pintype "bidirectional"))
    )
    (net (code "134") (name "unconnected-(J2-Pad59)") (class "Default")
      (node (ref "J2") (pin "59") (pinfunction "59_59") (pintype "bidirectional"))
    )
    (net (code "135") (name "unconnected-(J2-Pad60)") (class "Default")
      (node (ref "J2") (pin "60") (pinfunction "60_60") (pintype "bidirectional"))
    )
    (net (code "136") (name "unconnected-(J2-Pad63)") (class "Default")
      (node (ref "J2") (pin "63") (pinfunction "63_63") (pintype "bidirectional"))
    )
    (net (code "137") (name "unconnected-(J2-Pad64)") (class "Default")
      (node (ref "J2") (pin "64") (pinfunction "64_64") (pintype "bidirectional"))
    )
    (net (code "138") (name "unconnected-(J2-Pad65)") (class "Default")
      (node (ref "J2") (pin "65") (pinfunction "65_65") (pintype "bidirectional"))
    )
    (net (code "139") (name "unconnected-(J2-Pad66)") (class "Default")
      (node (ref "J2") (pin "66") (pinfunction "66_66") (pintype "bidirectional"))
    )
    (net (code "140") (name "unconnected-(J2-Pad69)") (class "Default")
      (node (ref "J2") (pin "69") (pinfunction "69_69") (pintype "bidirectional"))
    )
    (net (code "141") (name "unconnected-(J2-Pad71)") (class "Default")
      (node (ref "J2") (pin "71") (pinfunction "71_71") (pintype "bidirectional"))
    )
    (net (code "142") (name "unconnected-(J2-Pad75)") (class "Default")
      (node (ref "J2") (pin "75") (pinfunction "75_75") (pintype "bidirectional"))
    )
    (net (code "143") (name "unconnected-(J2-Pad77)") (class "Default")
      (node (ref "J2") (pin "77") (pinfunction "77_77") (pintype "bidirectional"))
    )
    (net (code "144") (name "unconnected-(J2-Pad81)") (class "Default")
      (node (ref "J2") (pin "81") (pinfunction "81_81") (pintype "bidirectional"))
    )
    (net (code "145") (name "unconnected-(J2-Pad83)") (class "Default")
      (node (ref "J2") (pin "83") (pinfunction "83_83") (pintype "bidirectional"))
    )
    (net (code "146") (name "unconnected-(J2-Pad87)") (class "Default")
      (node (ref "J2") (pin "87") (pinfunction "87_87") (pintype "bidirectional"))
    )
    (net (code "147") (name "unconnected-(J2-Pad89)") (class "Default")
      (node (ref "J2") (pin "89") (pinfunction "89_89") (pintype "bidirectional"))
    )
    (net (code "148") (name "unconnected-(J2-Pad93)") (class "Default")
      (node (ref "J2") (pin "93") (pinfunction "93_93") (pintype "bidirectional"))
    )
    (net (code "149") (name "unconnected-(J2-Pad94)") (class "Default")
      (node (ref "J2") (pin "94") (pinfunction "94_94") (pintype "bidirectional"))
    )
    (net (code "150") (name "unconnected-(J2-Pad95)") (class "Default")
      (node (ref "J2") (pin "95") (pinfunction "95_95") (pintype "bidirectional"))
    )
    (net (code "151") (name "unconnected-(J2-Pad96)") (class "Default")
      (node (ref "J2") (pin "96") (pinfunction "96_96") (pintype "bidirectional"))
    )
    (net (code "152") (name "unconnected-(J3-DET-PadG5)") (class "Default")
      (node (ref "J3") (pin "G5") (pinfunction "DET_G5") (pintype "bidirectional"))
    )
    (net (code "153") (name "unconnected-(J3-POL-PadG4)") (class "Default")
      (node (ref "J3") (pin "G4") (pinfunction "POL_G4") (pintype "bidirectional"))
    )
    (net (code "154") (name "unconnected-(U$59-DN1-PadA7)") (class "Default")
      (node (ref "U$59") (pin "A7") (pinfunction "DN1_A7") (pintype "bidirectional"))
    )
    (net (code "155") (name "unconnected-(U$59-DN2-PadB7)") (class "Default")
      (node (ref "U$59") (pin "B7") (pinfunction "DN2_B7") (pintype "bidirectional"))
    )
    (net (code "156") (name "unconnected-(U$59-DP1-PadA6)") (class "Default")
      (node (ref "U$59") (pin "A6") (pinfunction "DP1_A6") (pintype "bidirectional"))
    )
    (net (code "157") (name "unconnected-(U$59-DP2-PadB6)") (class "Default")
      (node (ref "U$59") (pin "B6") (pinfunction "DP2_B6") (pintype "bidirectional"))
    )
    (net (code "158") (name "unconnected-(U$59-SBU1-PadA8)") (class "Default")
      (node (ref "U$59") (pin "A8") (pinfunction "SBU1_A8") (pintype "bidirectional"))
    )
    (net (code "159") (name "unconnected-(U$59-SBU2-PadB8)") (class "Default")
      (node (ref "U$59") (pin "B8") (pinfunction "SBU2_B8") (pintype "bidirectional"))
    )
  )
)
